# LZ3003_2.net
KiCad netlist of a schematic drawn in EAGLE
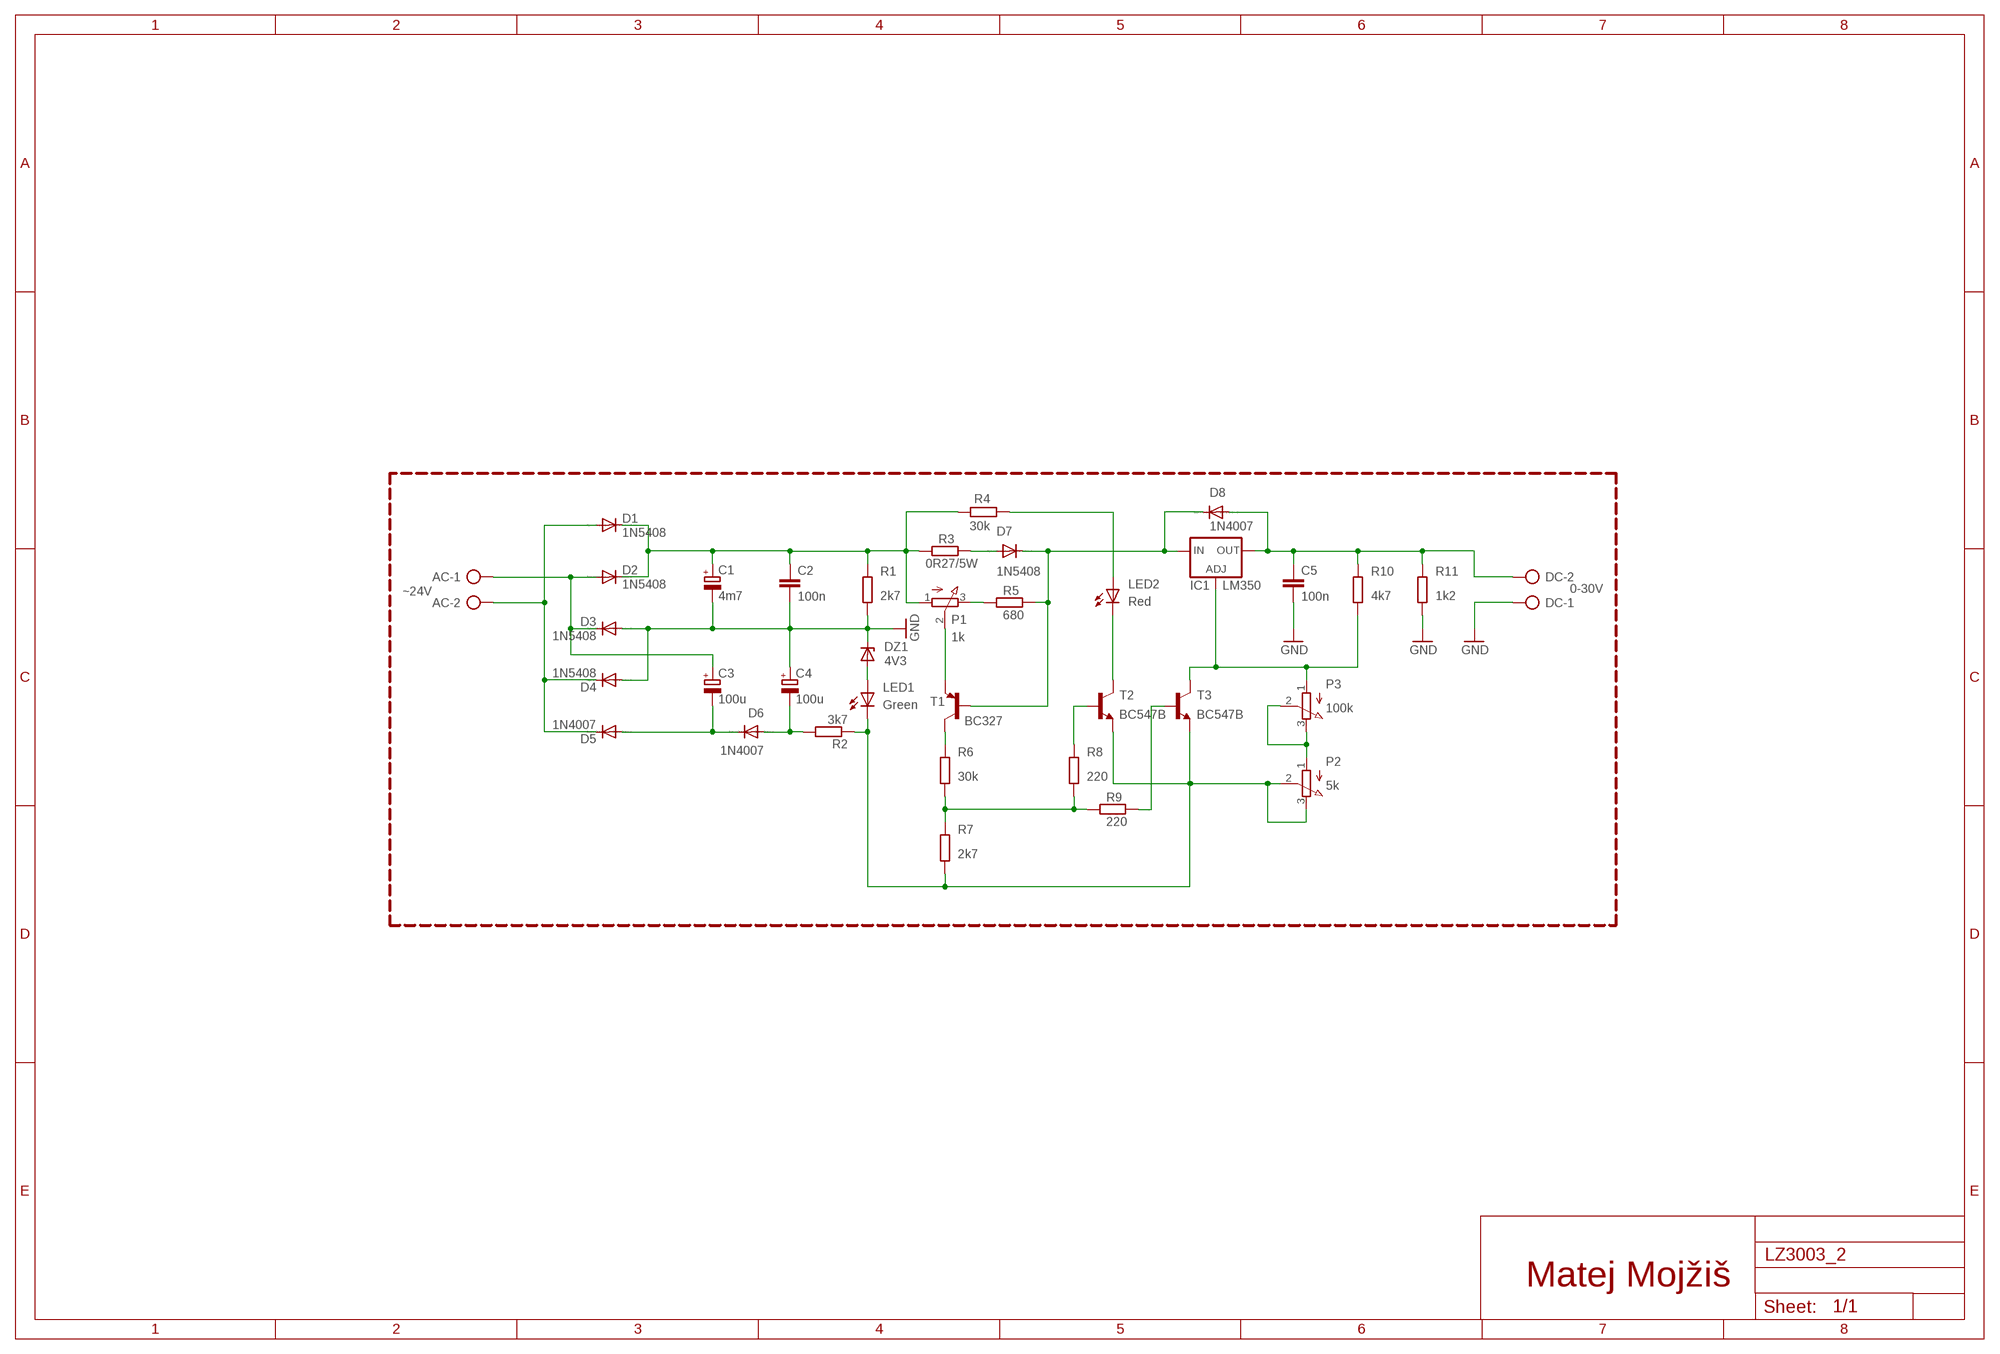
[diagram p0: schematic, sheet 1]

(export (version "E")
  (design (tool "Eeschema 10.0.6"))
  (components
    (comp (ref "AC")
      (value "~24V")
      (footprint "eagle-import:W237-102")
      (fields (field (name "MPN") "237-102"))
      (libsource (lib "eagle-import") (part "W237-102"))
    )
    (comp (ref "C1")
      (value "4m7")
      (footprint "eagle-import:E7,5-16")
      (libsource (lib "eagle-import") (part "CPOL-EUE7.5-16"))
    )
    (comp (ref "C2")
      (value "100n")
      (footprint "eagle-import:C050-025X075")
      (libsource (lib "eagle-import") (part "C-EU050-025X075"))
    )
    (comp (ref "C3")
      (value "100u")
      (footprint "eagle-import:E5-8,5")
      (libsource (lib "eagle-import") (part "CPOL-EUE5-8.5"))
    )
    (comp (ref "C4")
      (value "100u")
      (footprint "eagle-import:E5-8,5")
      (libsource (lib "eagle-import") (part "CPOL-EUE5-8.5"))
    )
    (comp (ref "C5")
      (value "100n")
      (footprint "eagle-import:C050-025X075")
      (libsource (lib "eagle-import") (part "C-EU050-025X075"))
    )
    (comp (ref "D1")
      (value "1N5408")
      (footprint "eagle-import:DO201-15")
      (libsource (lib "eagle-import") (part "1N5400"))
    )
    (comp (ref "D2")
      (value "1N5408")
      (footprint "eagle-import:DO201-15")
      (libsource (lib "eagle-import") (part "1N5400"))
    )
    (comp (ref "D3")
      (value "1N5408")
      (footprint "eagle-import:DO201-15")
      (libsource (lib "eagle-import") (part "1N5400"))
    )
    (comp (ref "D4")
      (value "1N5408")
      (footprint "eagle-import:DO201-15")
      (libsource (lib "eagle-import") (part "1N5400"))
    )
    (comp (ref "D5")
      (value "1N4007")
      (footprint "eagle-import:DO41-10")
      (libsource (lib "eagle-import") (part "1N4004"))
    )
    (comp (ref "D6")
      (value "1N4007")
      (footprint "eagle-import:DO41-10")
      (libsource (lib "eagle-import") (part "1N4004"))
    )
    (comp (ref "D7")
      (value "1N5408")
      (footprint "eagle-import:DO201-15")
      (libsource (lib "eagle-import") (part "1N5400"))
    )
    (comp (ref "D8")
      (value "1N4007")
      (footprint "eagle-import:DO41-10")
      (libsource (lib "eagle-import") (part "1N4004"))
    )
    (comp (ref "DC")
      (value "0-30V")
      (footprint "eagle-import:W237-102")
      (fields (field (name "MPN") "237-102"))
      (libsource (lib "eagle-import") (part "W237-102"))
    )
    (comp (ref "DZ1")
      (value "4V3")
      (footprint "eagle-import:DO34Z7")
      (libsource (lib "eagle-import") (part "ZENER-DIODEDO34-7"))
    )
    (comp (ref "IC1")
      (value "LM350")
      (footprint "eagle-import:317TS")
      (libsource (lib "eagle-import") (part "LM317TS"))
    )
    (comp (ref "LED1")
      (value "Green")
      (footprint "eagle-import:LED5MM")
      (libsource (lib "eagle-import") (part "LED5MM"))
    )
    (comp (ref "LED2")
      (value "Red")
      (footprint "eagle-import:LED5MM")
      (libsource (lib "eagle-import") (part "LED5MM"))
    )
    (comp (ref "P1")
      (value "1k")
      (footprint "eagle-import:3RP_1610N")
      (libsource (lib "eagle-import") (part "3RP/1610N"))
    )
    (comp (ref "P2")
      (value "5k")
      (footprint "eagle-import:3RP_1610N")
      (libsource (lib "eagle-import") (part "3RP/1610N"))
    )
    (comp (ref "P3")
      (value "100k")
      (footprint "eagle-import:3RP_1610N")
      (libsource (lib "eagle-import") (part "3RP/1610N"))
    )
    (comp (ref "R1")
      (value "2k7")
      (footprint "eagle-import:0207_7")
      (libsource (lib "eagle-import") (part "R-EU_0207/7"))
    )
    (comp (ref "R2")
      (value "3k7")
      (footprint "eagle-import:0207_7")
      (libsource (lib "eagle-import") (part "R-EU_0207/7"))
    )
    (comp (ref "R3")
      (value "0R27/5W")
      (footprint "eagle-import:0617_22")
      (libsource (lib "eagle-import") (part "R-EU_0617/22"))
    )
    (comp (ref "R4")
      (value "30k")
      (footprint "eagle-import:0207_7")
      (libsource (lib "eagle-import") (part "R-EU_0207/7"))
    )
    (comp (ref "R5")
      (value "680")
      (footprint "eagle-import:0207_7")
      (libsource (lib "eagle-import") (part "R-EU_0207/7"))
    )
    (comp (ref "R6")
      (value "30k")
      (footprint "eagle-import:0207_7")
      (libsource (lib "eagle-import") (part "R-EU_0207/7"))
    )
    (comp (ref "R7")
      (value "2k7")
      (footprint "eagle-import:0207_7")
      (libsource (lib "eagle-import") (part "R-EU_0207/7"))
    )
    (comp (ref "R8")
      (value "220")
      (footprint "eagle-import:0207_7")
      (libsource (lib "eagle-import") (part "R-EU_0207/7"))
    )
    (comp (ref "R9")
      (value "220")
      (footprint "eagle-import:0207_7")
      (libsource (lib "eagle-import") (part "R-EU_0207/7"))
    )
    (comp (ref "R10")
      (value "4k7")
      (footprint "eagle-import:0207_7")
      (libsource (lib "eagle-import") (part "R-EU_0207/7"))
    )
    (comp (ref "R11")
      (value "1k2")
      (footprint "eagle-import:0207_7")
      (libsource (lib "eagle-import") (part "R-EU_0207/7"))
    )
    (comp (ref "T1")
      (value "BC327")
      (footprint "eagle-import:TO92-EBC")
      (libsource (lib "eagle-import") (part "BC327"))
    )
    (comp (ref "T2")
      (value "BC547B")
      (footprint "eagle-import:TO92-CBE")
      (libsource (lib "eagle-import") (part "-NPN-TO92-CBEBC547B"))
    )
    (comp (ref "T3")
      (value "BC547B")
      (footprint "eagle-import:TO92-CBE")
      (libsource (lib "eagle-import") (part "-NPN-TO92-CBEBC547B"))
    )
  )
  (nets
    (net (code "1") (name "GND") (class "Default")
      (node (ref "C1") (pin "-") (pinfunction "-_-") (pintype "passive"))
      (node (ref "C2") (pin "2") (pinfunction "2_2") (pintype "passive"))
      (node (ref "C4") (pin "+") (pinfunction "+_+") (pintype "passive"))
      (node (ref "C5") (pin "2") (pinfunction "2_2") (pintype "passive"))
      (node (ref "D3") (pin "A") (pinfunction "A_A") (pintype "passive"))
      (node (ref "D4") (pin "A") (pinfunction "A_A") (pintype "passive"))
      (node (ref "DC") (pin "1") (pinfunction "KL_1") (pintype "passive"))
      (node (ref "DZ1") (pin "C") (pinfunction "C_C") (pintype "passive"))
      (node (ref "R1") (pin "2") (pinfunction "2_2") (pintype "passive"))
      (node (ref "R11") (pin "1") (pinfunction "1_1") (pintype "passive"))
    )
    (net (code "2") (name "Net-(ACA-KL)") (class "Default")
      (node (ref "AC") (pin "1") (pinfunction "KL_1") (pintype "passive"))
      (node (ref "C3") (pin "+") (pinfunction "+_+") (pintype "passive"))
      (node (ref "D2") (pin "A") (pinfunction "A_A") (pintype "passive"))
      (node (ref "D3") (pin "C") (pinfunction "C_C") (pintype "passive"))
    )
    (net (code "3") (name "Net-(ACB-KL)") (class "Default")
      (node (ref "AC") (pin "2") (pinfunction "KL_2") (pintype "passive"))
      (node (ref "D1") (pin "A") (pinfunction "A_A") (pintype "passive"))
      (node (ref "D4") (pin "C") (pinfunction "C_C") (pintype "passive"))
      (node (ref "D5") (pin "C") (pinfunction "C_C") (pintype "passive"))
    )
    (net (code "4") (name "Net-(C3-Pad-)") (class "Default")
      (node (ref "C3") (pin "-") (pinfunction "-_-") (pintype "passive"))
      (node (ref "D5") (pin "A") (pinfunction "A_A") (pintype "passive"))
      (node (ref "D6") (pin "C") (pinfunction "C_C") (pintype "passive"))
    )
    (net (code "5") (name "Net-(C4-Pad-)") (class "Default")
      (node (ref "C4") (pin "-") (pinfunction "-_-") (pintype "passive"))
      (node (ref "D6") (pin "A") (pinfunction "A_A") (pintype "passive"))
      (node (ref "R2") (pin "2") (pinfunction "2_2") (pintype "passive"))
    )
    (net (code "6") (name "Net-(D7-PadA)") (class "Default")
      (node (ref "D7") (pin "A") (pinfunction "A_A") (pintype "passive"))
      (node (ref "R3") (pin "2") (pinfunction "2_2") (pintype "passive"))
    )
    (net (code "7") (name "Net-(DCB-KL)") (class "Default")
      (node (ref "C5") (pin "1") (pinfunction "1_1") (pintype "passive"))
      (node (ref "D8") (pin "A") (pinfunction "A_A") (pintype "passive"))
      (node (ref "DC") (pin "2") (pinfunction "KL_2") (pintype "passive"))
      (node (ref "IC1") (pin "2") (pinfunction "OUT_2") (pintype "passive"))
      (node (ref "R10") (pin "2") (pinfunction "2_2") (pintype "passive"))
      (node (ref "R11") (pin "2") (pinfunction "2_2") (pintype "passive"))
    )
    (net (code "8") (name "Net-(DZ1-PadA)") (class "Default")
      (node (ref "DZ1") (pin "A") (pinfunction "A_A") (pintype "passive"))
      (node (ref "LED1") (pin "A") (pinfunction "A_A") (pintype "passive"))
    )
    (net (code "9") (name "Net-(IC1-ADJ)") (class "Default")
      (node (ref "IC1") (pin "1") (pinfunction "ADJ_1") (pintype "input"))
      (node (ref "P3") (pin "1") (pinfunction "A_1") (pintype "passive"))
      (node (ref "R10") (pin "1") (pinfunction "1_1") (pintype "passive"))
      (node (ref "T3") (pin "C") (pinfunction "C_C") (pintype "passive"))
    )
    (net (code "10") (name "Net-(IC1-IN)") (class "Default")
      (node (ref "D7") (pin "C") (pinfunction "C_C") (pintype "passive"))
      (node (ref "D8") (pin "C") (pinfunction "C_C") (pintype "passive"))
      (node (ref "IC1") (pin "3") (pinfunction "IN_3") (pintype "input"))
      (node (ref "R5") (pin "2") (pinfunction "2_2") (pintype "passive"))
      (node (ref "T1") (pin "B") (pinfunction "B_B") (pintype "passive"))
    )
    (net (code "11") (name "Net-(LED1-C)") (class "Default")
      (node (ref "LED1") (pin "K") (pinfunction "C_K") (pintype "passive"))
      (node (ref "P2") (pin "2") (pinfunction "S_2") (pintype "passive"))
      (node (ref "P2") (pin "3") (pinfunction "E_3") (pintype "passive"))
      (node (ref "R2") (pin "1") (pinfunction "1_1") (pintype "passive"))
      (node (ref "R7") (pin "1") (pinfunction "1_1") (pintype "passive"))
      (node (ref "T2") (pin "E") (pinfunction "E_E") (pintype "passive"))
      (node (ref "T3") (pin "E") (pinfunction "E_E") (pintype "passive"))
    )
    (net (code "12") (name "Net-(LED2-C)") (class "Default")
      (node (ref "LED2") (pin "K") (pinfunction "C_K") (pintype "passive"))
      (node (ref "T2") (pin "C") (pinfunction "C_C") (pintype "passive"))
    )
    (net (code "13") (name "Net-(LED2-PadA)") (class "Default")
      (node (ref "LED2") (pin "A") (pinfunction "A_A") (pintype "passive"))
      (node (ref "R4") (pin "1") (pinfunction "1_1") (pintype "passive"))
    )
    (net (code "14") (name "Net-(P1-A)") (class "Default")
      (node (ref "C1") (pin "+") (pinfunction "+_+") (pintype "passive"))
      (node (ref "C2") (pin "1") (pinfunction "1_1") (pintype "passive"))
      (node (ref "D1") (pin "C") (pinfunction "C_C") (pintype "passive"))
      (node (ref "D2") (pin "C") (pinfunction "C_C") (pintype "passive"))
      (node (ref "P1") (pin "1") (pinfunction "A_1") (pintype "passive"))
      (node (ref "R1") (pin "1") (pinfunction "1_1") (pintype "passive"))
      (node (ref "R3") (pin "1") (pinfunction "1_1") (pintype "passive"))
      (node (ref "R4") (pin "2") (pinfunction "2_2") (pintype "passive"))
    )
    (net (code "15") (name "Net-(P1-E)") (class "Default")
      (node (ref "P1") (pin "3") (pinfunction "E_3") (pintype "passive"))
      (node (ref "R5") (pin "1") (pinfunction "1_1") (pintype "passive"))
    )
    (net (code "16") (name "Net-(P1-S)") (class "Default")
      (node (ref "P1") (pin "2") (pinfunction "S_2") (pintype "passive"))
      (node (ref "T1") (pin "E") (pinfunction "E_E") (pintype "passive"))
    )
    (net (code "17") (name "Net-(P2-A)") (class "Default")
      (node (ref "P2") (pin "1") (pinfunction "A_1") (pintype "passive"))
      (node (ref "P3") (pin "2") (pinfunction "S_2") (pintype "passive"))
      (node (ref "P3") (pin "3") (pinfunction "E_3") (pintype "passive"))
    )
    (net (code "18") (name "Net-(R6-Pad1)") (class "Default")
      (node (ref "R6") (pin "1") (pinfunction "1_1") (pintype "passive"))
      (node (ref "R7") (pin "2") (pinfunction "2_2") (pintype "passive"))
      (node (ref "R8") (pin "1") (pinfunction "1_1") (pintype "passive"))
      (node (ref "R9") (pin "1") (pinfunction "1_1") (pintype "passive"))
    )
    (net (code "19") (name "Net-(R6-Pad2)") (class "Default")
      (node (ref "R6") (pin "2") (pinfunction "2_2") (pintype "passive"))
      (node (ref "T1") (pin "C") (pinfunction "C_C") (pintype "passive"))
    )
    (net (code "20") (name "Net-(R8-Pad2)") (class "Default")
      (node (ref "R8") (pin "2") (pinfunction "2_2") (pintype "passive"))
      (node (ref "T2") (pin "B") (pinfunction "B_B") (pintype "passive"))
    )
    (net (code "21") (name "Net-(R9-Pad2)") (class "Default")
      (node (ref "R9") (pin "2") (pinfunction "2_2") (pintype "passive"))
      (node (ref "T3") (pin "B") (pinfunction "B_B") (pintype "passive"))
    )
  )
)
